# dengenn_top.net
KiCad netlist of a schematic drawn in EAGLE
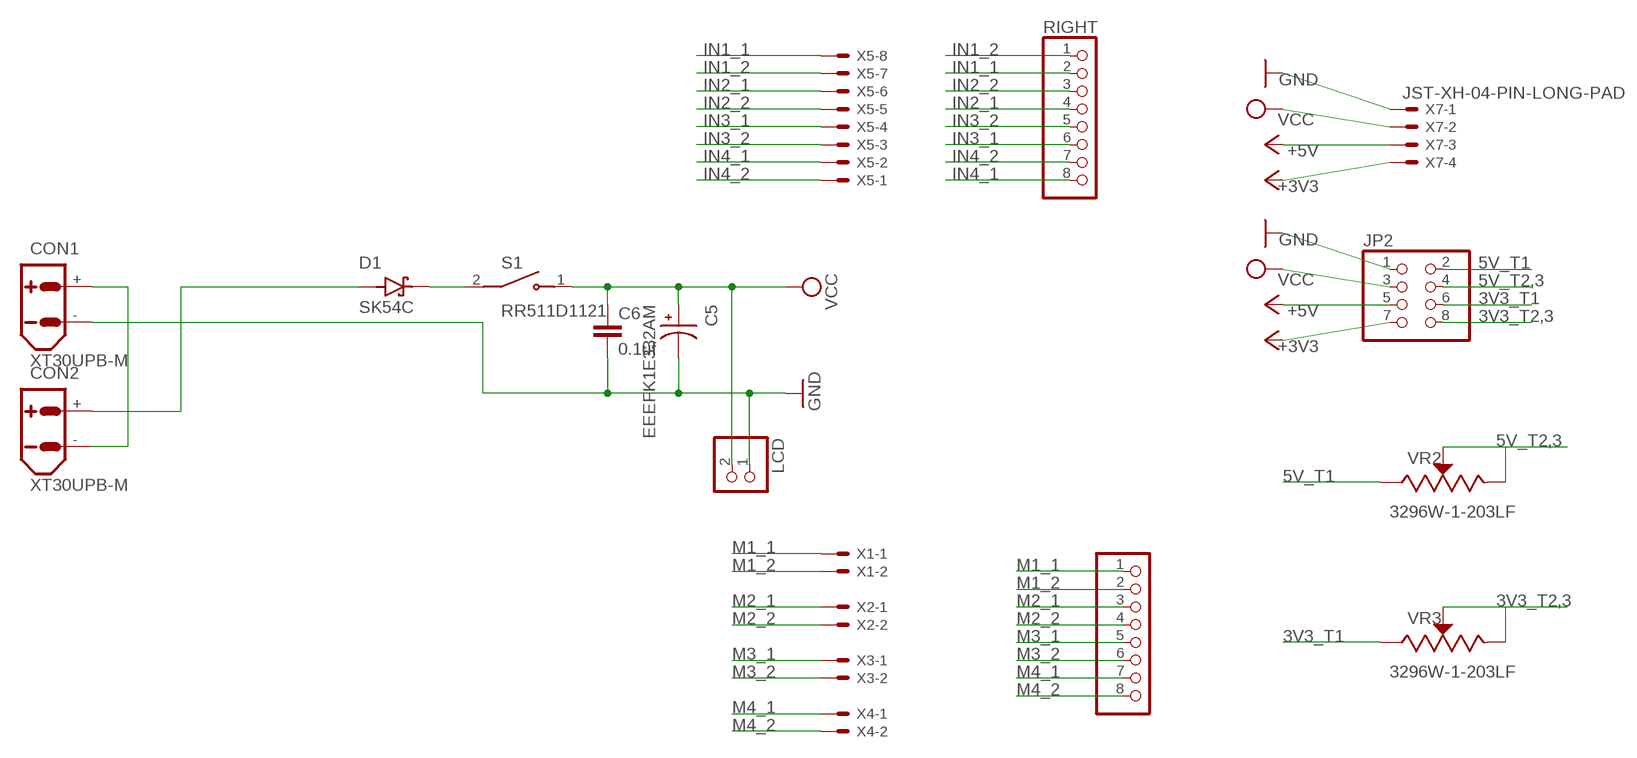
[diagram p0: schematic, sheet 1]

(export (version "E")
  (design (tool "Eeschema 10.0.6"))
  (components
    (comp (ref "C5")
      (value "EEEFK1E332AM")
      (footprint "eagle-import:CAP_EEEFK1E332AM")
      (fields (field (name "MF") "Panasonic"))
      (libsource (lib "eagle-import") (part "EEEFK1E332AM"))
    )
    (comp (ref "C6")
      (value "0.1uf")
      (footprint "eagle-import:C0603")
      (libsource (lib "eagle-import") (part "C-EUC0603"))
    )
    (comp (ref "CON1")
      (value "XT30UPB-M")
      (footprint "eagle-import:XT30UPB-M")
      (libsource (lib "eagle-import") (part "XT30UPB-M"))
    )
    (comp (ref "CON2")
      (value "XT30UPB-M")
      (footprint "eagle-import:XT30UPB-M")
      (libsource (lib "eagle-import") (part "XT30UPB-M"))
    )
    (comp (ref "D1")
      (value "SK54C")
      (footprint "eagle-import:DIOM6859X262N")
      (fields (field (name "MF") "Taiwan Semiconductor"))
      (libsource (lib "eagle-import") (part "SK54C"))
    )
    (comp (ref "JP2")
      (value "PINHD-2X4")
      (footprint "eagle-import:2X04")
      (libsource (lib "eagle-import") (part "PINHD-2X4"))
    )
    (comp (ref "LCD")
      (value "PINHD-1X2")
      (footprint "eagle-import:1X02")
      (libsource (lib "eagle-import") (part "PINHD-1X2"))
    )
    (comp (ref "LEFT")
      (value "PINHD-1X8")
      (footprint "eagle-import:1X08")
      (libsource (lib "eagle-import") (part "PINHD-1X8"))
    )
    (comp (ref "RIGHT")
      (value "PINHD-1X8")
      (footprint "eagle-import:1X08")
      (libsource (lib "eagle-import") (part "PINHD-1X8"))
    )
    (comp (ref "S1")
      (value "RR511D1121")
      (footprint "eagle-import:E-SWITCH_RR511D1121")
      (fields (field (name "MF") "E-Switch"))
      (libsource (lib "eagle-import") (part "RR511D1121"))
    )
    (comp (ref "VR2")
      (value "3296W-1-203LF")
      (footprint "eagle-import:TRIM_3296W-1-203LF")
      (fields (field (name "MF") "Bourns"))
      (libsource (lib "eagle-import") (part "3296W-1-203LF"))
    )
    (comp (ref "VR3")
      (value "3296W-1-203LF")
      (footprint "eagle-import:TRIM_3296W-1-203LF")
      (fields (field (name "MF") "Bourns"))
      (libsource (lib "eagle-import") (part "3296W-1-203LF"))
    )
    (comp (ref "X1")
      (value "JST-XH-02-PIN-LONG-PAD")
      (footprint "eagle-import:JST-XH-02-PACKAGE-LONG-PAD")
      (libsource (lib "eagle-import") (part "JST-XH-02-PIN-LONG-PAD"))
    )
    (comp (ref "X2")
      (value "JST-XH-02-PIN-LONG-PAD")
      (footprint "eagle-import:JST-XH-02-PACKAGE-LONG-PAD")
      (libsource (lib "eagle-import") (part "JST-XH-02-PIN-LONG-PAD"))
    )
    (comp (ref "X3")
      (value "JST-XH-02-PIN-LONG-PAD")
      (footprint "eagle-import:JST-XH-02-PACKAGE-LONG-PAD")
      (libsource (lib "eagle-import") (part "JST-XH-02-PIN-LONG-PAD"))
    )
    (comp (ref "X4")
      (value "JST-XH-02-PIN-LONG-PAD")
      (footprint "eagle-import:JST-XH-02-PACKAGE-LONG-PAD")
      (libsource (lib "eagle-import") (part "JST-XH-02-PIN-LONG-PAD"))
    )
    (comp (ref "X5")
      (value "JST-XH-08-PIN-ROUND-PAD")
      (footprint "eagle-import:JST-XH-08-PACKAGE-ROUND-PAD")
      (libsource (lib "eagle-import") (part "JST-XH-08-PIN-ROUND-PAD"))
    )
    (comp (ref "X7")
      (value "JST-XH-04-PIN-LONG-PAD")
      (footprint "eagle-import:JST-XH-04-PACKAGE-LONG-PAD")
      (libsource (lib "eagle-import") (part "JST-XH-04-PIN-LONG-PAD"))
    )
  )
  (nets
    (net (code "1") (name "+3V3") (class "Default")
      (node (ref "JP2") (pin "7") (pinfunction "7_7") (pintype "passive"))
      (node (ref "X7") (pin "4") (pinfunction "S_4") (pintype "passive"))
    )
    (net (code "2") (name "+5V") (class "Default")
      (node (ref "JP2") (pin "5") (pinfunction "5_5") (pintype "passive"))
      (node (ref "X7") (pin "3") (pinfunction "S_3") (pintype "passive"))
    )
    (net (code "3") (name "/3V3_T1") (class "Default")
      (node (ref "JP2") (pin "6") (pinfunction "6_6") (pintype "passive"))
      (node (ref "VR3") (pin "1") (pinfunction "CCW_1") (pintype "passive"))
    )
    (net (code "4") (name "/3V3_T2,3") (class "Default")
      (node (ref "JP2") (pin "8") (pinfunction "8_8") (pintype "passive"))
      (node (ref "VR3") (pin "2") (pinfunction "WIPER_2") (pintype "passive"))
      (node (ref "VR3") (pin "3") (pinfunction "CW_3") (pintype "passive"))
    )
    (net (code "5") (name "/5V_T1") (class "Default")
      (node (ref "JP2") (pin "2") (pinfunction "2_2") (pintype "passive"))
      (node (ref "VR2") (pin "1") (pinfunction "CCW_1") (pintype "passive"))
    )
    (net (code "6") (name "/5V_T2,3") (class "Default")
      (node (ref "JP2") (pin "4") (pinfunction "4_4") (pintype "passive"))
      (node (ref "VR2") (pin "2") (pinfunction "WIPER_2") (pintype "passive"))
      (node (ref "VR2") (pin "3") (pinfunction "CW_3") (pintype "passive"))
    )
    (net (code "7") (name "/IN1_1") (class "Default")
      (node (ref "RIGHT") (pin "2") (pinfunction "2_2") (pintype "passive"))
      (node (ref "X5") (pin "8") (pinfunction "S_8") (pintype "passive"))
    )
    (net (code "8") (name "/IN1_2") (class "Default")
      (node (ref "RIGHT") (pin "1") (pinfunction "1_1") (pintype "passive"))
      (node (ref "X5") (pin "7") (pinfunction "S_7") (pintype "passive"))
    )
    (net (code "9") (name "/IN2_1") (class "Default")
      (node (ref "RIGHT") (pin "4") (pinfunction "4_4") (pintype "passive"))
      (node (ref "X5") (pin "6") (pinfunction "S_6") (pintype "passive"))
    )
    (net (code "10") (name "/IN2_2") (class "Default")
      (node (ref "RIGHT") (pin "3") (pinfunction "3_3") (pintype "passive"))
      (node (ref "X5") (pin "5") (pinfunction "S_5") (pintype "passive"))
    )
    (net (code "11") (name "/IN3_1") (class "Default")
      (node (ref "RIGHT") (pin "6") (pinfunction "6_6") (pintype "passive"))
      (node (ref "X5") (pin "4") (pinfunction "S_4") (pintype "passive"))
    )
    (net (code "12") (name "/IN3_2") (class "Default")
      (node (ref "RIGHT") (pin "5") (pinfunction "5_5") (pintype "passive"))
      (node (ref "X5") (pin "3") (pinfunction "S_3") (pintype "passive"))
    )
    (net (code "13") (name "/IN4_1") (class "Default")
      (node (ref "RIGHT") (pin "8") (pinfunction "8_8") (pintype "passive"))
      (node (ref "X5") (pin "2") (pinfunction "S_2") (pintype "passive"))
    )
    (net (code "14") (name "/IN4_2") (class "Default")
      (node (ref "RIGHT") (pin "7") (pinfunction "7_7") (pintype "passive"))
      (node (ref "X5") (pin "1") (pinfunction "S_1") (pintype "passive"))
    )
    (net (code "15") (name "/M1_1") (class "Default")
      (node (ref "LEFT") (pin "1") (pinfunction "1_1") (pintype "passive"))
      (node (ref "X1") (pin "1") (pinfunction "S_1") (pintype "passive"))
    )
    (net (code "16") (name "/M1_2") (class "Default")
      (node (ref "LEFT") (pin "2") (pinfunction "2_2") (pintype "passive"))
      (node (ref "X1") (pin "2") (pinfunction "S_2") (pintype "passive"))
    )
    (net (code "17") (name "/M2_1") (class "Default")
      (node (ref "LEFT") (pin "3") (pinfunction "3_3") (pintype "passive"))
      (node (ref "X2") (pin "1") (pinfunction "S_1") (pintype "passive"))
    )
    (net (code "18") (name "/M2_2") (class "Default")
      (node (ref "LEFT") (pin "4") (pinfunction "4_4") (pintype "passive"))
      (node (ref "X2") (pin "2") (pinfunction "S_2") (pintype "passive"))
    )
    (net (code "19") (name "/M3_1") (class "Default")
      (node (ref "LEFT") (pin "5") (pinfunction "5_5") (pintype "passive"))
      (node (ref "X3") (pin "1") (pinfunction "S_1") (pintype "passive"))
    )
    (net (code "20") (name "/M3_2") (class "Default")
      (node (ref "LEFT") (pin "6") (pinfunction "6_6") (pintype "passive"))
      (node (ref "X3") (pin "2") (pinfunction "S_2") (pintype "passive"))
    )
    (net (code "21") (name "/M4_1") (class "Default")
      (node (ref "LEFT") (pin "7") (pinfunction "7_7") (pintype "passive"))
      (node (ref "X4") (pin "1") (pinfunction "S_1") (pintype "passive"))
    )
    (net (code "22") (name "/M4_2") (class "Default")
      (node (ref "LEFT") (pin "8") (pinfunction "8_8") (pintype "passive"))
      (node (ref "X4") (pin "2") (pinfunction "S_2") (pintype "passive"))
    )
    (net (code "23") (name "GND") (class "Default")
      (node (ref "C5") (pin "2") (pinfunction "2_2") (pintype "passive"))
      (node (ref "C6") (pin "2") (pinfunction "2_2") (pintype "passive"))
      (node (ref "CON1") (pin "-") (pinfunction "-_-") (pintype "power_in"))
      (node (ref "JP2") (pin "1") (pinfunction "1_1") (pintype "passive"))
      (node (ref "LCD") (pin "1") (pinfunction "1_1") (pintype "passive"))
      (node (ref "X7") (pin "1") (pinfunction "S_1") (pintype "passive"))
    )
    (net (code "24") (name "Net-(CON1-Pad+)") (class "Default")
      (node (ref "CON1") (pin "+") (pinfunction "+_+") (pintype "power_in"))
      (node (ref "CON2") (pin "-") (pinfunction "-_-") (pintype "power_in"))
    )
    (net (code "25") (name "Net-(CON2-Pad+)") (class "Default")
      (node (ref "CON2") (pin "+") (pinfunction "+_+") (pintype "power_in"))
      (node (ref "D1") (pin "A") (pinfunction "A_A") (pintype "passive"))
    )
    (net (code "26") (name "Net-(D1-K)") (class "Default")
      (node (ref "D1") (pin "C") (pinfunction "K_C") (pintype "passive"))
      (node (ref "S1") (pin "2") (pinfunction "COM_2") (pintype "passive"))
    )
    (net (code "27") (name "VCC") (class "Default")
      (node (ref "C5") (pin "1") (pinfunction "1_1") (pintype "passive"))
      (node (ref "C6") (pin "1") (pinfunction "1_1") (pintype "passive"))
      (node (ref "JP2") (pin "3") (pinfunction "3_3") (pintype "passive"))
      (node (ref "LCD") (pin "2") (pinfunction "2_2") (pintype "passive"))
      (node (ref "S1") (pin "1") (pinfunction "NO_1") (pintype "passive"))
      (node (ref "X7") (pin "2") (pinfunction "S_2") (pintype "passive"))
    )
  )
)
